# sensor.net
KiCad netlist of a schematic drawn in EAGLE
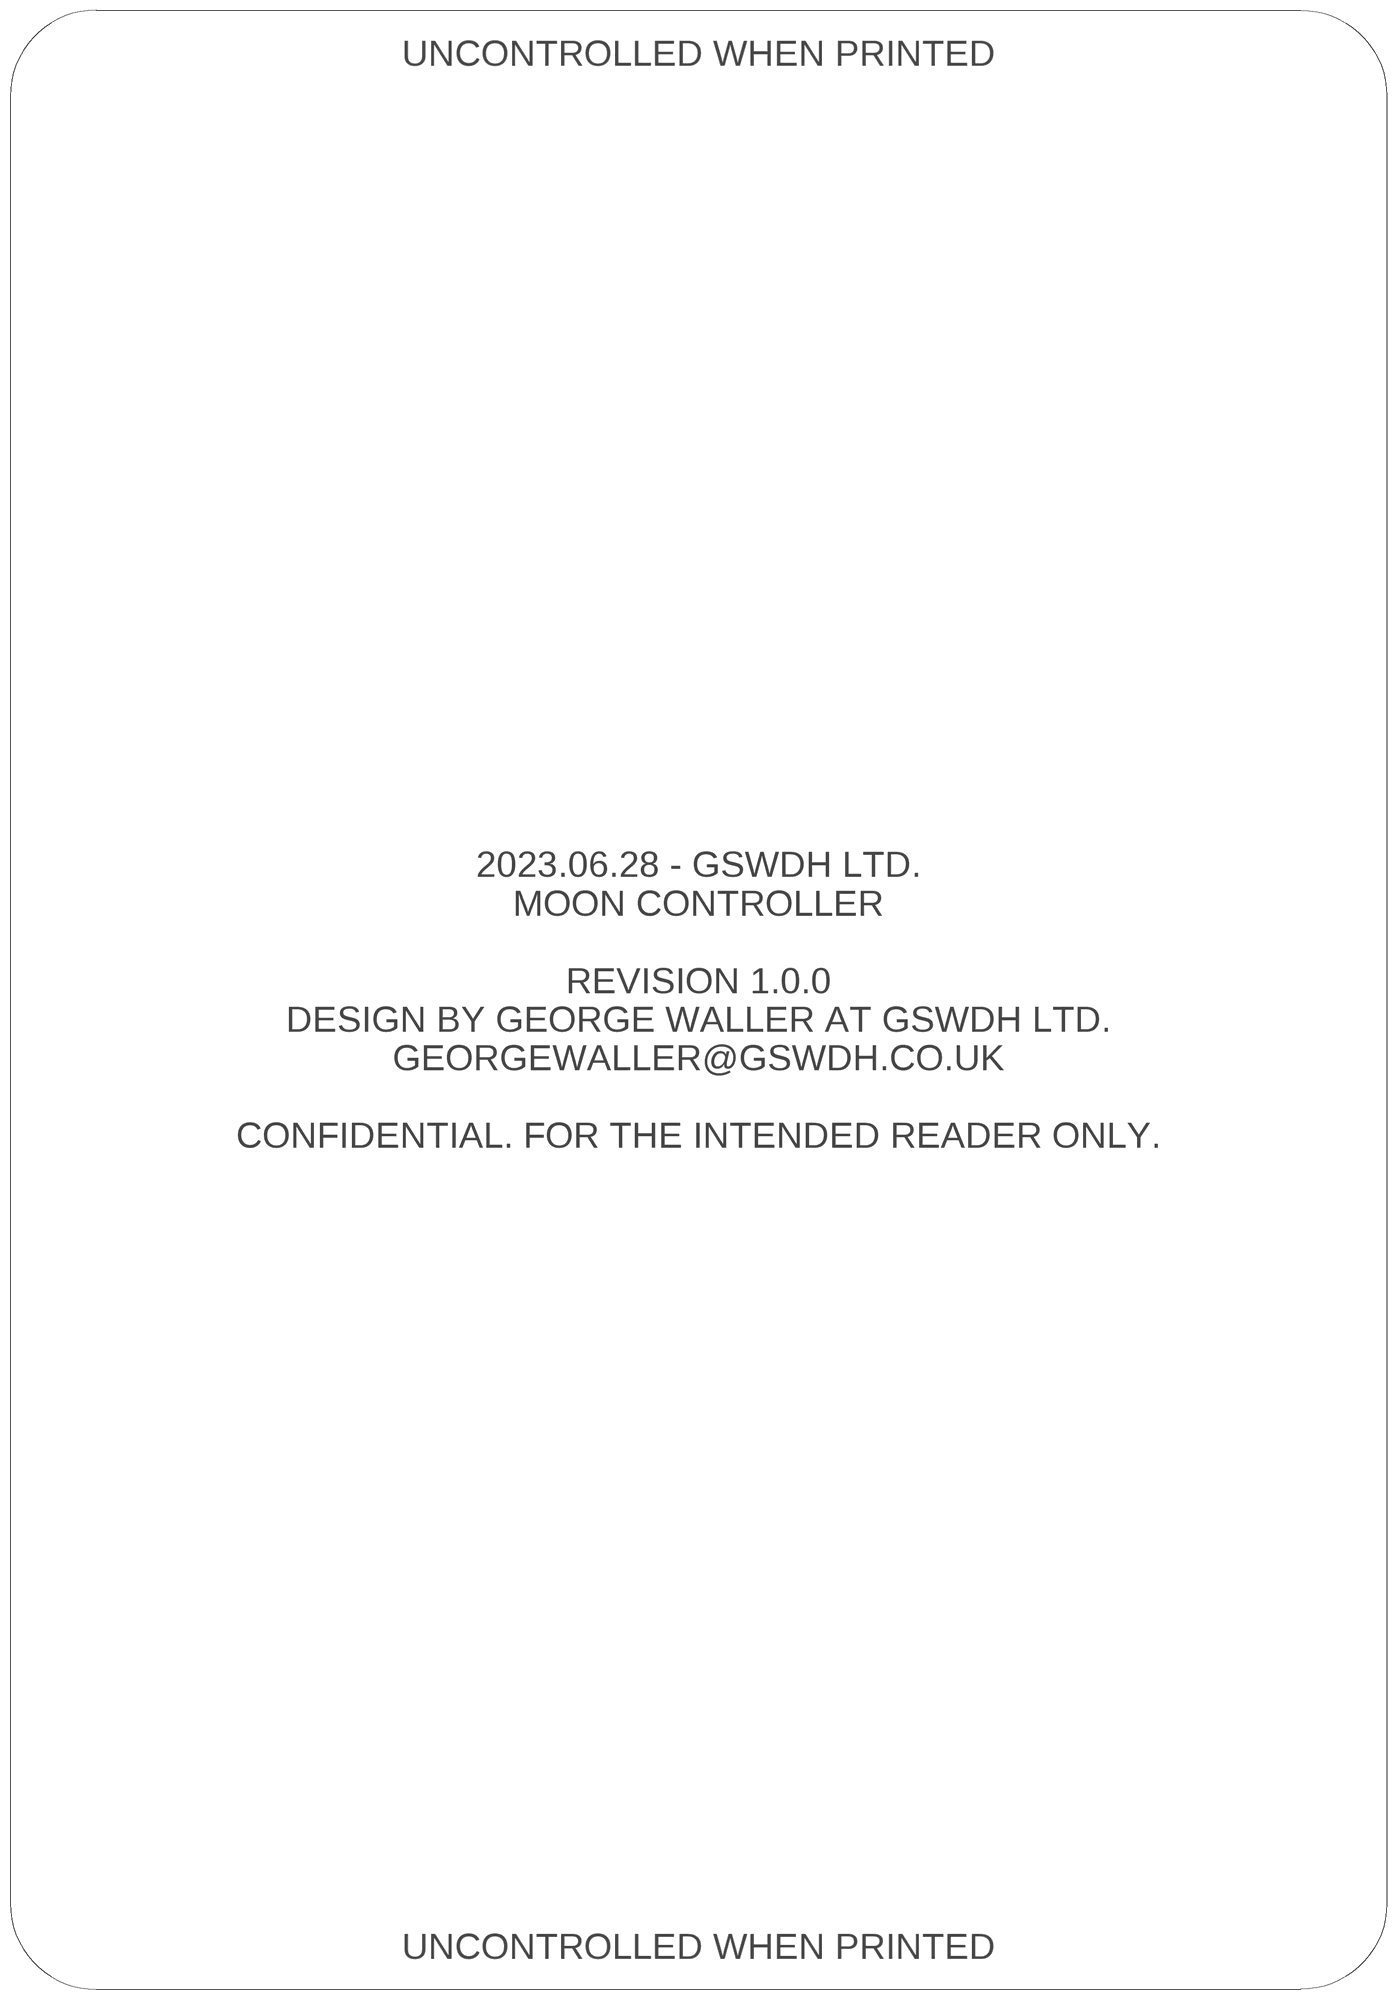
[diagram p0: schematic, sheet 1]
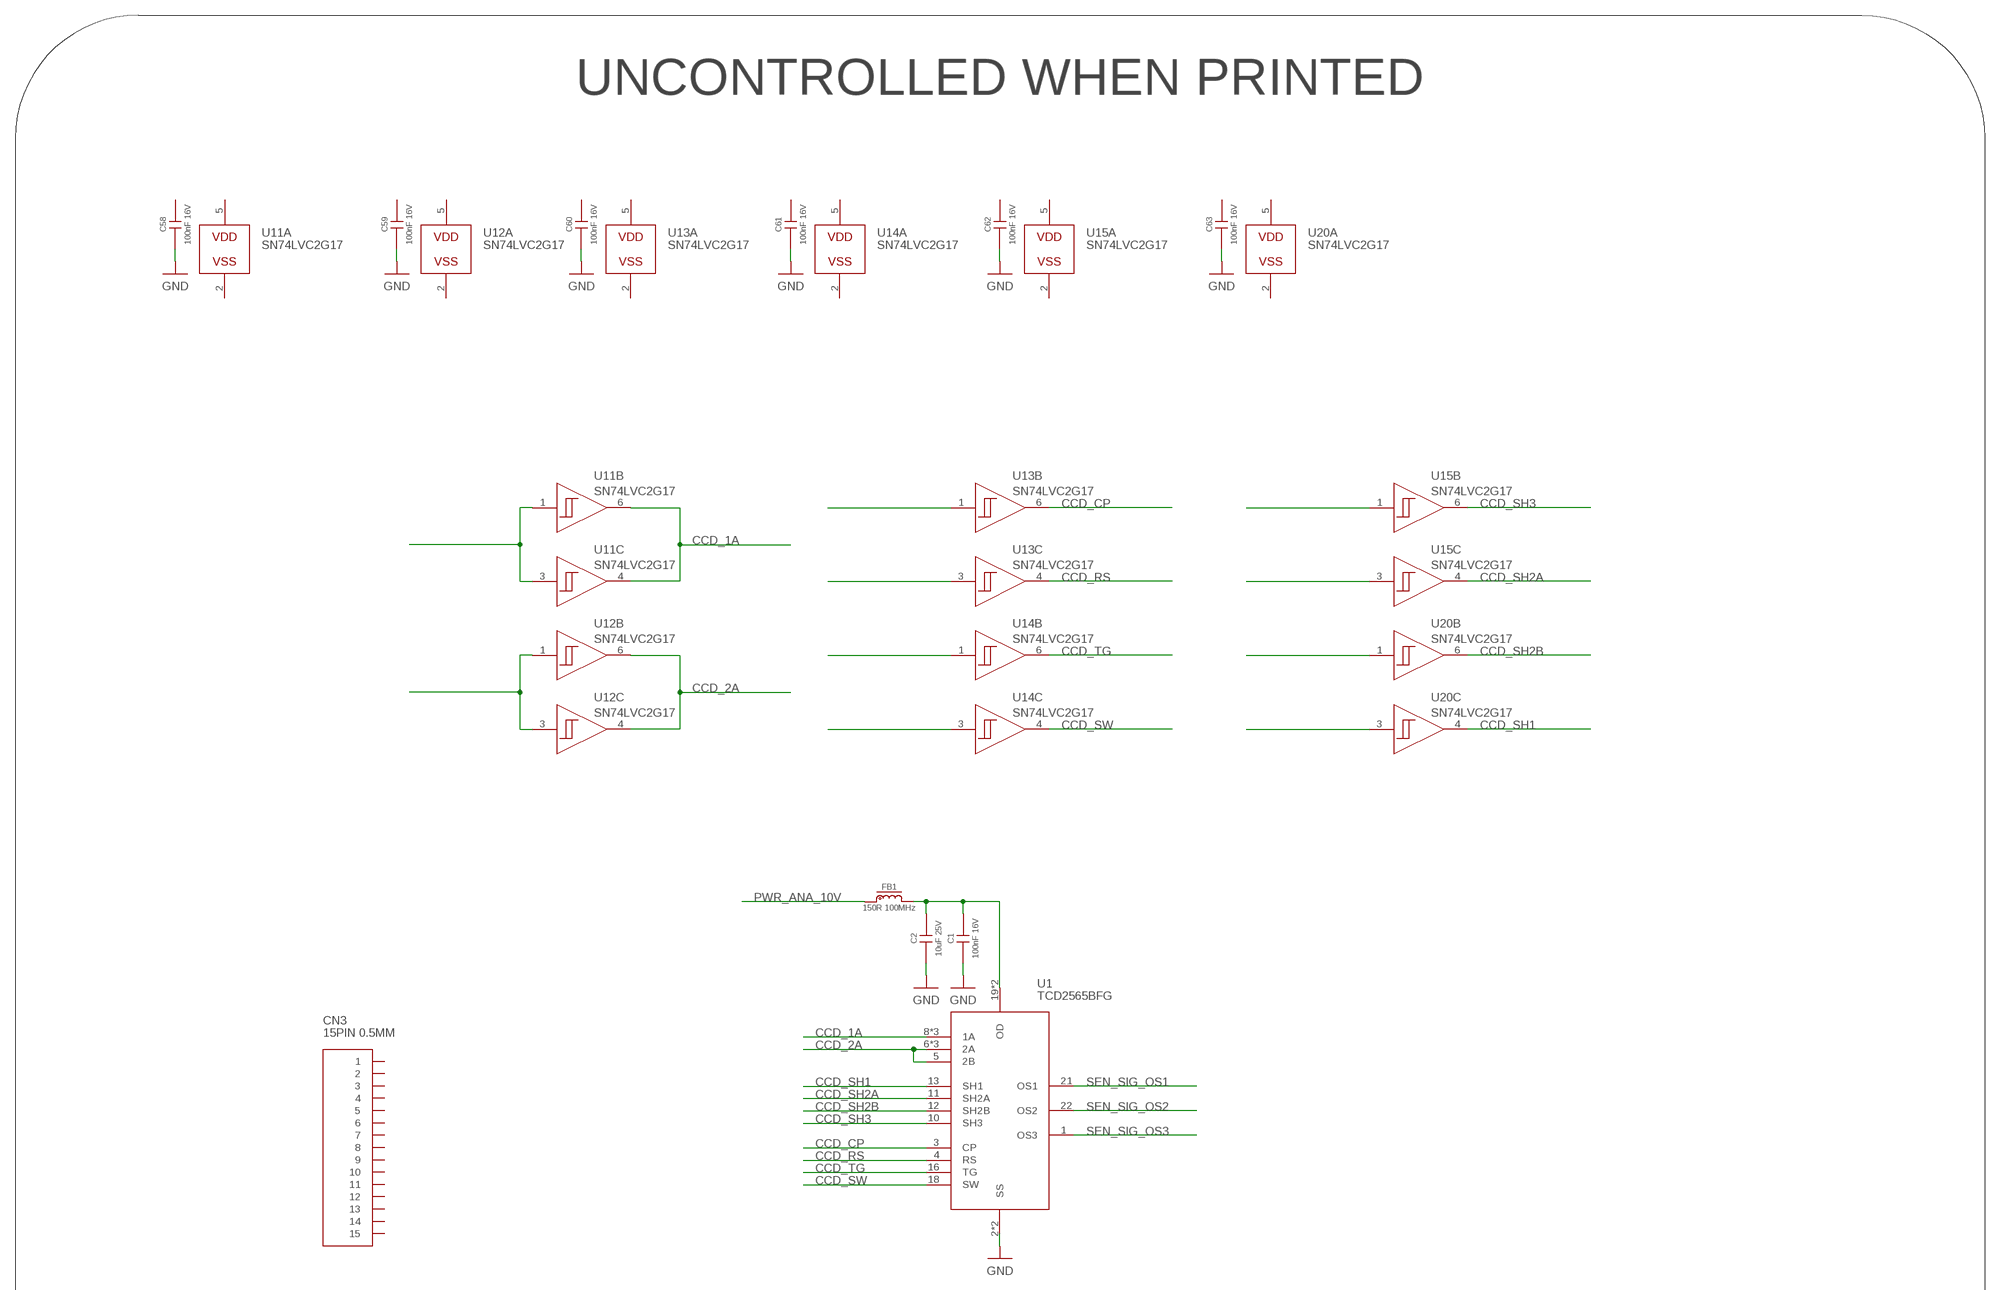
[diagram p1: schematic, sheet 2, part 1 of 2]
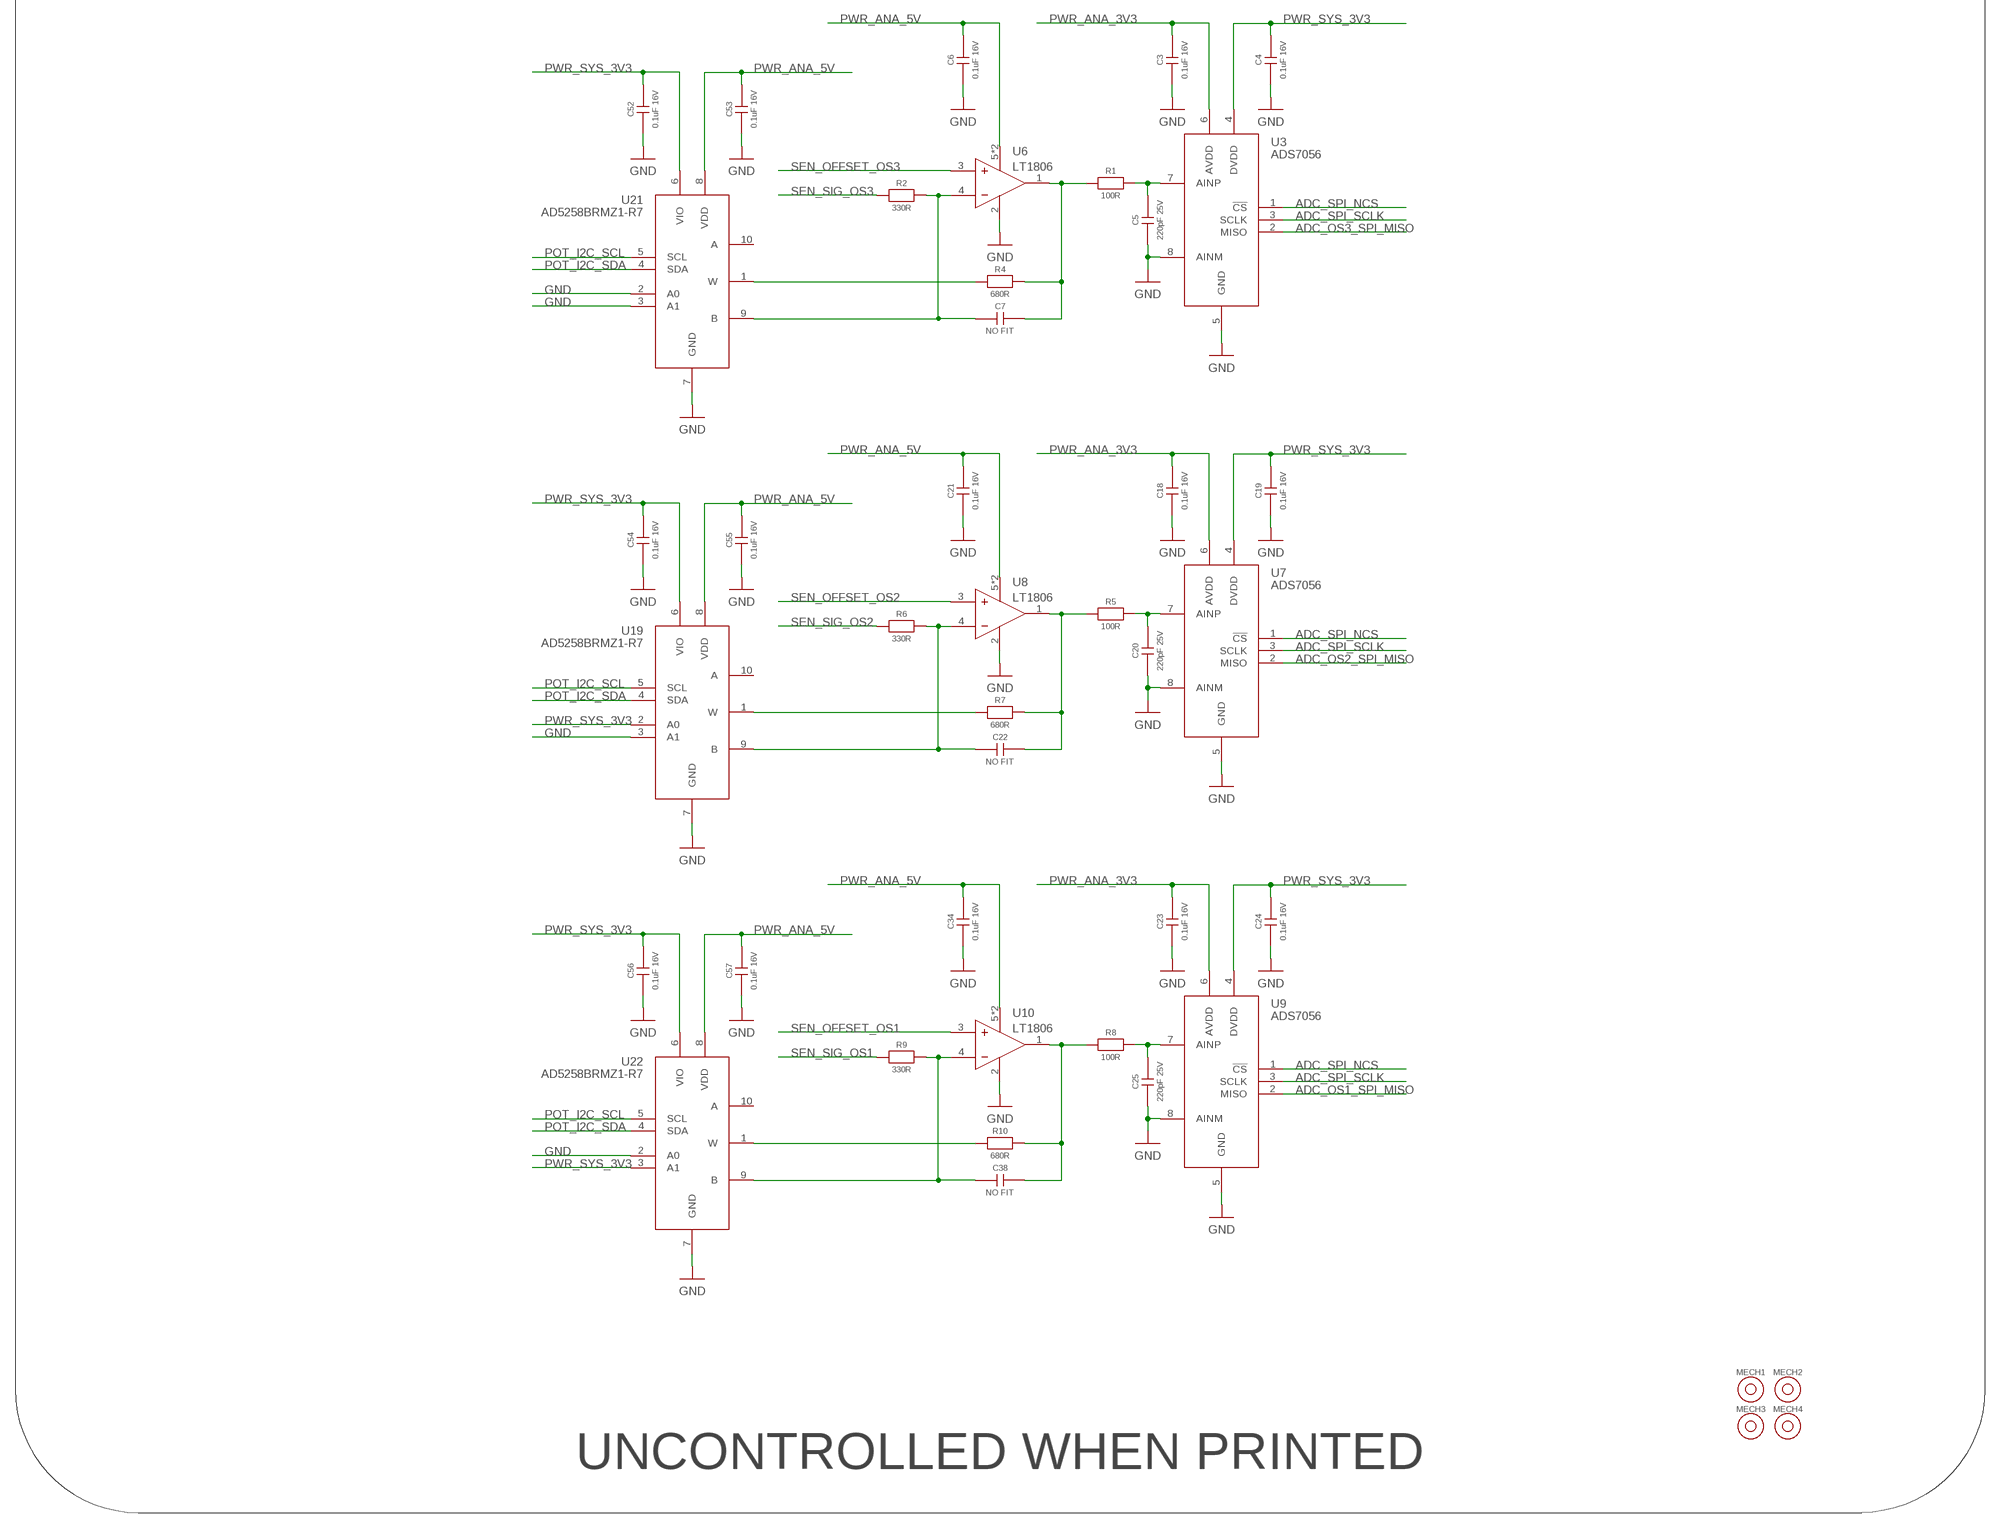
[diagram p2: schematic, sheet 2, part 2 of 2]
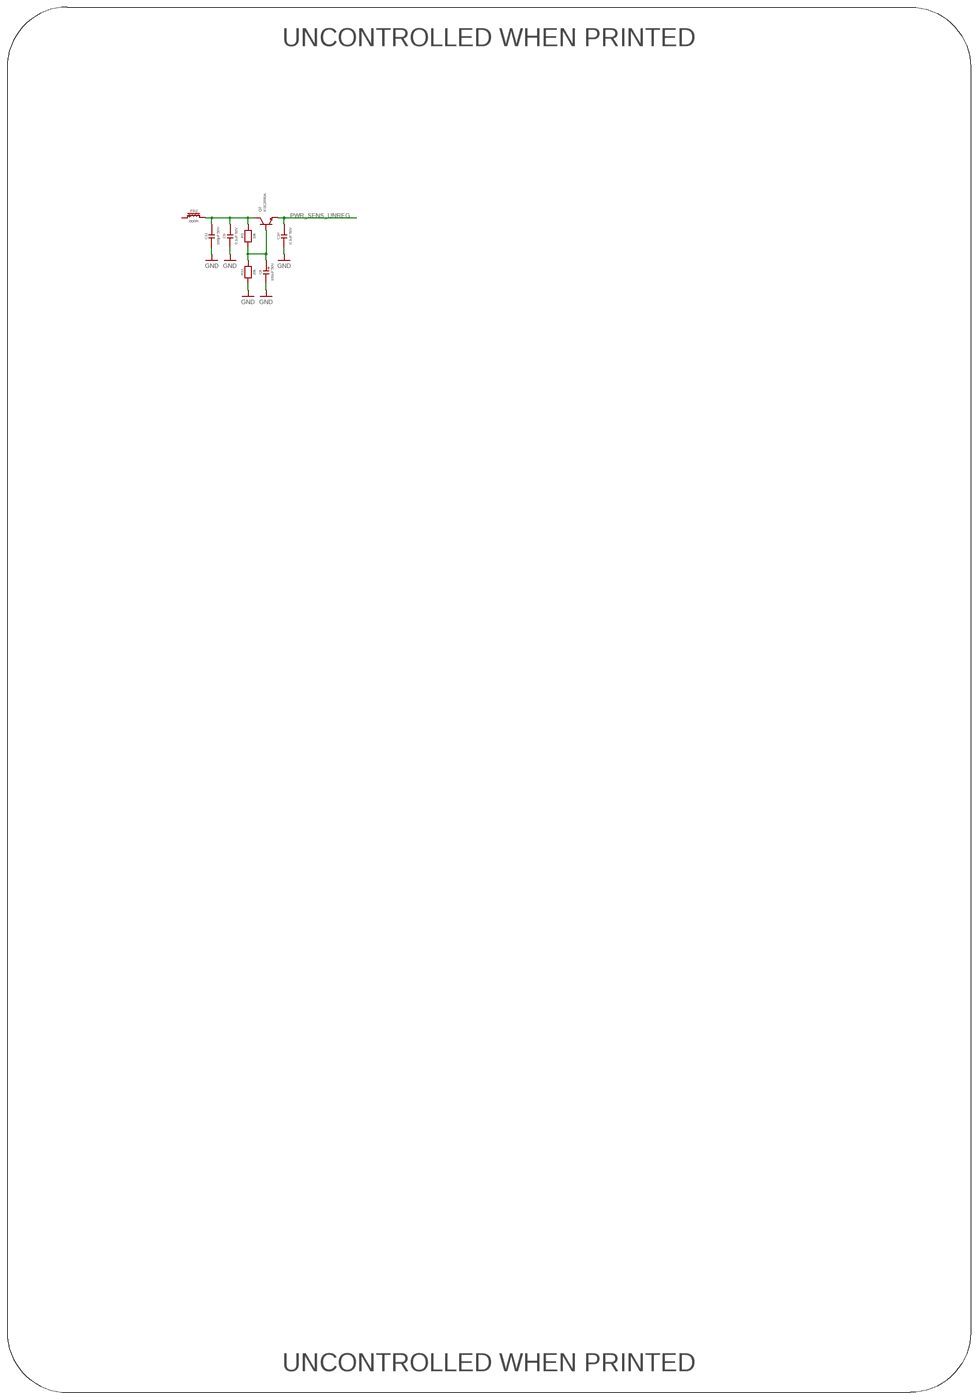
[diagram p3: schematic, sheet 3, overview]
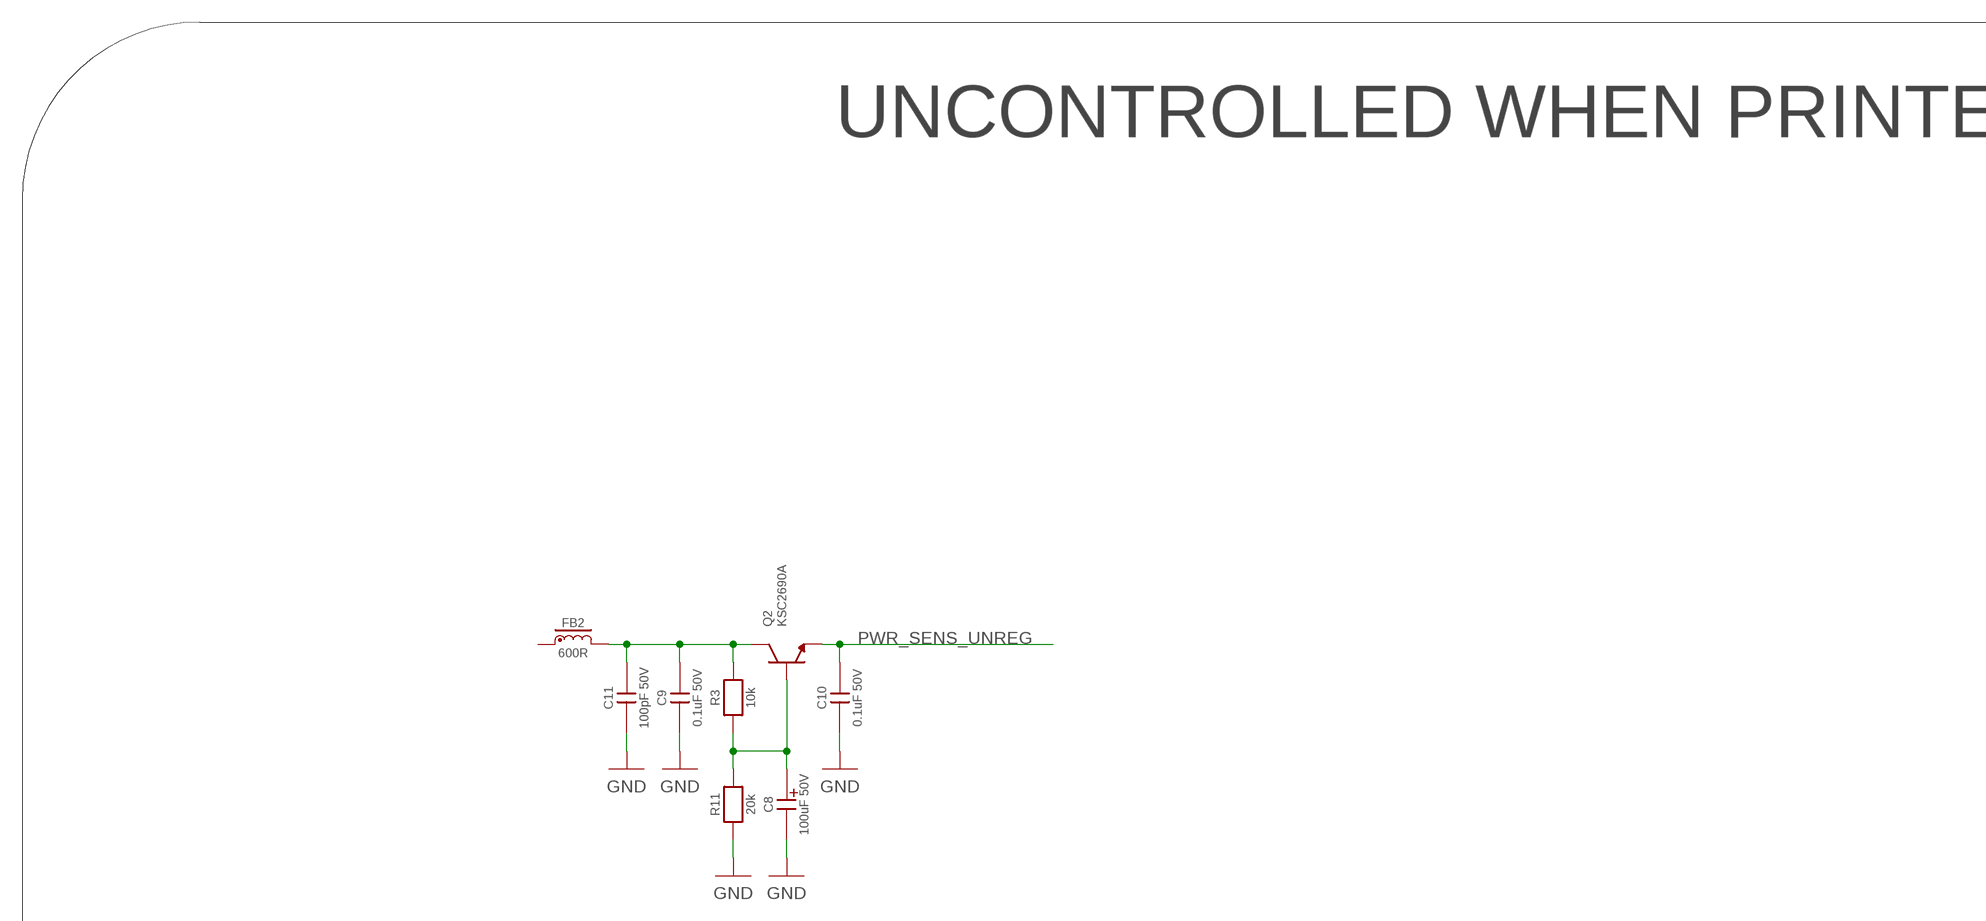
[diagram p4: schematic, sheet 3, part 1 of 4]
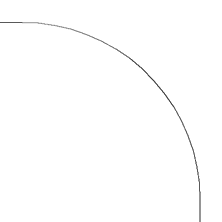
[diagram p5: schematic, sheet 3, part 2 of 4]
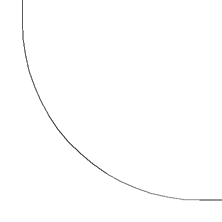
[diagram p6: schematic, sheet 3, part 3 of 4]
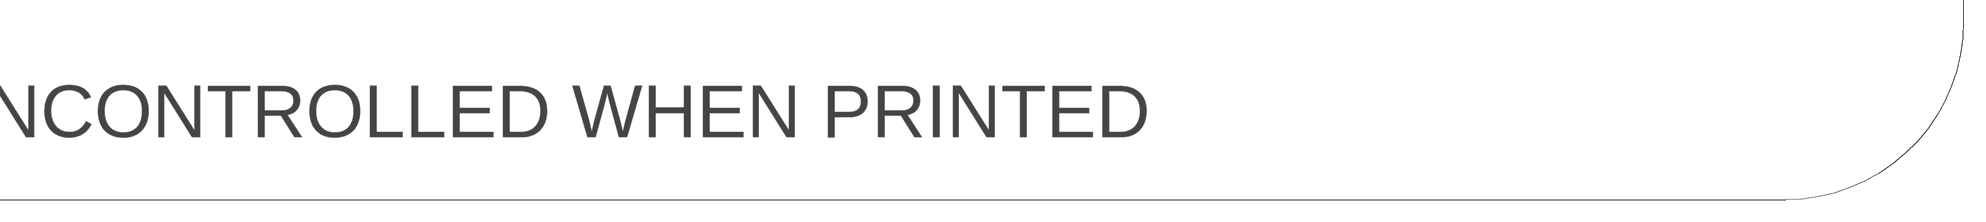
[diagram p7: schematic, sheet 3, part 4 of 4]

(export (version "E")
  (design (tool "Eeschema 10.0.6"))
  (components
    (comp (ref "C1")
      (value "100nF 16V")
      (footprint "eagle-import:0603")
      (libsource (lib "eagle-import") (part "CL10B104KO8WPNC"))
    )
    (comp (ref "C2")
      (value "10uF 25V")
      (footprint "eagle-import:1206")
      (fields
        (field (name "MANUFACTURER") "KEMET")
        (field (name "TOLERANCE") "±10%")
        (field (name "VOLTAGE") "25V")
      )
      (libsource (lib "eagle-import") (part "C1206C106K3RACAUTO"))
    )
    (comp (ref "C3")
      (value "0.1uF 16V")
      (footprint "eagle-import:0402")
      (fields
        (field (name "MANUFACTURER") "AVX Corporation")
        (field (name "TOLERANCE") "±10%")
        (field (name "VOLTAGE") "16V")
      )
      (libsource (lib "eagle-import") (part "0402YC104KAT2A"))
    )
    (comp (ref "C4")
      (value "0.1uF 16V")
      (footprint "eagle-import:0402")
      (fields
        (field (name "MANUFACTURER") "AVX Corporation")
        (field (name "TOLERANCE") "±10%")
        (field (name "VOLTAGE") "16V")
      )
      (libsource (lib "eagle-import") (part "0402YC104KAT2A"))
    )
    (comp (ref "C5")
      (value "220pF 25V")
      (footprint "eagle-import:0402")
      (fields
        (field (name "MANUFACTURER") "AVX Corporation")
        (field (name "TOLERANCE") "±1%")
        (field (name "VOLTAGE") "25V")
      )
      (libsource (lib "eagle-import") (part "04023A221FAT2A"))
    )
    (comp (ref "C6")
      (value "0.1uF 16V")
      (footprint "eagle-import:0402")
      (fields
        (field (name "MANUFACTURER") "AVX Corporation")
        (field (name "TOLERANCE") "±10%")
        (field (name "VOLTAGE") "16V")
      )
      (libsource (lib "eagle-import") (part "0402YC104KAT2A"))
    )
    (comp (ref "C7")
      (value "NO FIT")
      (footprint "eagle-import:0402")
      (fields
        (field (name "MANUFACTURER") "KEMET")
        (field (name "TOLERANCE") "±5%")
        (field (name "VOLTAGE") "25V")
      )
      (libsource (lib "eagle-import") (part "C0402C100J3GACAUTO"))
    )
    (comp (ref "C18")
      (value "0.1uF 16V")
      (footprint "eagle-import:0402")
      (fields
        (field (name "MANUFACTURER") "AVX Corporation")
        (field (name "TOLERANCE") "±10%")
        (field (name "VOLTAGE") "16V")
      )
      (libsource (lib "eagle-import") (part "0402YC104KAT2A"))
    )
    (comp (ref "C19")
      (value "0.1uF 16V")
      (footprint "eagle-import:0402")
      (fields
        (field (name "MANUFACTURER") "AVX Corporation")
        (field (name "TOLERANCE") "±10%")
        (field (name "VOLTAGE") "16V")
      )
      (libsource (lib "eagle-import") (part "0402YC104KAT2A"))
    )
    (comp (ref "C20")
      (value "220pF 25V")
      (footprint "eagle-import:0402")
      (fields
        (field (name "MANUFACTURER") "AVX Corporation")
        (field (name "TOLERANCE") "±1%")
        (field (name "VOLTAGE") "25V")
      )
      (libsource (lib "eagle-import") (part "04023A221FAT2A"))
    )
    (comp (ref "C21")
      (value "0.1uF 16V")
      (footprint "eagle-import:0402")
      (fields
        (field (name "MANUFACTURER") "AVX Corporation")
        (field (name "TOLERANCE") "±10%")
        (field (name "VOLTAGE") "16V")
      )
      (libsource (lib "eagle-import") (part "0402YC104KAT2A"))
    )
    (comp (ref "C22")
      (value "NO FIT")
      (footprint "eagle-import:0402")
      (fields
        (field (name "MANUFACTURER") "KEMET")
        (field (name "TOLERANCE") "±5%")
        (field (name "VOLTAGE") "25V")
      )
      (libsource (lib "eagle-import") (part "C0402C100J3GACAUTO"))
    )
    (comp (ref "C23")
      (value "0.1uF 16V")
      (footprint "eagle-import:0402")
      (fields
        (field (name "MANUFACTURER") "AVX Corporation")
        (field (name "TOLERANCE") "±10%")
        (field (name "VOLTAGE") "16V")
      )
      (libsource (lib "eagle-import") (part "0402YC104KAT2A"))
    )
    (comp (ref "C24")
      (value "0.1uF 16V")
      (footprint "eagle-import:0402")
      (fields
        (field (name "MANUFACTURER") "AVX Corporation")
        (field (name "TOLERANCE") "±10%")
        (field (name "VOLTAGE") "16V")
      )
      (libsource (lib "eagle-import") (part "0402YC104KAT2A"))
    )
    (comp (ref "C25")
      (value "220pF 25V")
      (footprint "eagle-import:0402")
      (fields
        (field (name "MANUFACTURER") "AVX Corporation")
        (field (name "TOLERANCE") "±1%")
        (field (name "VOLTAGE") "25V")
      )
      (libsource (lib "eagle-import") (part "04023A221FAT2A"))
    )
    (comp (ref "C34")
      (value "0.1uF 16V")
      (footprint "eagle-import:0402")
      (fields
        (field (name "MANUFACTURER") "AVX Corporation")
        (field (name "TOLERANCE") "±10%")
        (field (name "VOLTAGE") "16V")
      )
      (libsource (lib "eagle-import") (part "0402YC104KAT2A"))
    )
    (comp (ref "C38")
      (value "NO FIT")
      (footprint "eagle-import:0402")
      (fields
        (field (name "MANUFACTURER") "KEMET")
        (field (name "TOLERANCE") "±5%")
        (field (name "VOLTAGE") "25V")
      )
      (libsource (lib "eagle-import") (part "C0402C100J3GACAUTO"))
    )
    (comp (ref "C52")
      (value "0.1uF 16V")
      (footprint "eagle-import:0402")
      (fields
        (field (name "MANUFACTURER") "AVX Corporation")
        (field (name "TOLERANCE") "±10%")
        (field (name "VOLTAGE") "16V")
      )
      (libsource (lib "eagle-import") (part "0402YC104KAT2A"))
    )
    (comp (ref "C53")
      (value "0.1uF 16V")
      (footprint "eagle-import:0402")
      (fields
        (field (name "MANUFACTURER") "AVX Corporation")
        (field (name "TOLERANCE") "±10%")
        (field (name "VOLTAGE") "16V")
      )
      (libsource (lib "eagle-import") (part "0402YC104KAT2A"))
    )
    (comp (ref "C54")
      (value "0.1uF 16V")
      (footprint "eagle-import:0402")
      (fields
        (field (name "MANUFACTURER") "AVX Corporation")
        (field (name "TOLERANCE") "±10%")
        (field (name "VOLTAGE") "16V")
      )
      (libsource (lib "eagle-import") (part "0402YC104KAT2A"))
    )
    (comp (ref "C55")
      (value "0.1uF 16V")
      (footprint "eagle-import:0402")
      (fields
        (field (name "MANUFACTURER") "AVX Corporation")
        (field (name "TOLERANCE") "±10%")
        (field (name "VOLTAGE") "16V")
      )
      (libsource (lib "eagle-import") (part "0402YC104KAT2A"))
    )
    (comp (ref "C56")
      (value "0.1uF 16V")
      (footprint "eagle-import:0402")
      (fields
        (field (name "MANUFACTURER") "AVX Corporation")
        (field (name "TOLERANCE") "±10%")
        (field (name "VOLTAGE") "16V")
      )
      (libsource (lib "eagle-import") (part "0402YC104KAT2A"))
    )
    (comp (ref "C57")
      (value "0.1uF 16V")
      (footprint "eagle-import:0402")
      (fields
        (field (name "MANUFACTURER") "AVX Corporation")
        (field (name "TOLERANCE") "±10%")
        (field (name "VOLTAGE") "16V")
      )
      (libsource (lib "eagle-import") (part "0402YC104KAT2A"))
    )
    (comp (ref "C58")
      (value "100nF 16V")
      (footprint "eagle-import:0603")
      (libsource (lib "eagle-import") (part "CL10B104KO8WPNC"))
    )
    (comp (ref "C59")
      (value "100nF 16V")
      (footprint "eagle-import:0603")
      (libsource (lib "eagle-import") (part "CL10B104KO8WPNC"))
    )
    (comp (ref "C60")
      (value "100nF 16V")
      (footprint "eagle-import:0603")
      (libsource (lib "eagle-import") (part "CL10B104KO8WPNC"))
    )
    (comp (ref "C61")
      (value "100nF 16V")
      (footprint "eagle-import:0603")
      (libsource (lib "eagle-import") (part "CL10B104KO8WPNC"))
    )
    (comp (ref "C62")
      (value "100nF 16V")
      (footprint "eagle-import:0603")
      (libsource (lib "eagle-import") (part "CL10B104KO8WPNC"))
    )
    (comp (ref "C63")
      (value "100nF 16V")
      (footprint "eagle-import:0603")
      (libsource (lib "eagle-import") (part "CL10B104KO8WPNC"))
    )
    (comp (ref "CN3")
      (value "15PIN 0.5MM")
      (footprint "eagle-import:SFV15R-1STE1HLF")
      (libsource (lib "eagle-import") (part "SFV15R-1STE1HLF"))
    )
    (comp (ref "FB1")
      (value "150R 100MHz")
      (footprint "eagle-import:1206")
      (libsource (lib "eagle-import") (part "ILB1206ER151V"))
    )
    (comp (ref "MECH1")
      (value "6mm x 3mm")
      (footprint "eagle-import:MOUNTHOLE_6X3")
      (libsource (lib "eagle-import") (part "MOUNTHOLE"))
    )
    (comp (ref "MECH2")
      (value "6mm x 3mm")
      (footprint "eagle-import:MOUNTHOLE_6X3")
      (libsource (lib "eagle-import") (part "MOUNTHOLE"))
    )
    (comp (ref "MECH3")
      (value "6mm x 3mm")
      (footprint "eagle-import:MOUNTHOLE_6X3")
      (libsource (lib "eagle-import") (part "MOUNTHOLE"))
    )
    (comp (ref "MECH4")
      (value "6mm x 3mm")
      (footprint "eagle-import:MOUNTHOLE_6X3")
      (libsource (lib "eagle-import") (part "MOUNTHOLE"))
    )
    (comp (ref "R1")
      (value "100R")
      (footprint "eagle-import:0402")
      (libsource (lib "eagle-import") (part "RC0402FR-10100RL"))
    )
    (comp (ref "R2")
      (value "330R")
      (footprint "eagle-import:0402")
      (libsource (lib "eagle-import") (part "RC0402FR-07330RL"))
    )
    (comp (ref "R4")
      (value "680R")
      (footprint "eagle-import:0402")
      (libsource (lib "eagle-import") (part "RC0402FR-07680RL"))
    )
    (comp (ref "R5")
      (value "100R")
      (footprint "eagle-import:0402")
      (libsource (lib "eagle-import") (part "RC0402FR-10100RL"))
    )
    (comp (ref "R6")
      (value "330R")
      (footprint "eagle-import:0402")
      (libsource (lib "eagle-import") (part "RC0402FR-07330RL"))
    )
    (comp (ref "R7")
      (value "680R")
      (footprint "eagle-import:0402")
      (libsource (lib "eagle-import") (part "RC0402FR-07680RL"))
    )
    (comp (ref "R8")
      (value "100R")
      (footprint "eagle-import:0402")
      (libsource (lib "eagle-import") (part "RC0402FR-10100RL"))
    )
    (comp (ref "R9")
      (value "330R")
      (footprint "eagle-import:0402")
      (libsource (lib "eagle-import") (part "RC0402FR-07330RL"))
    )
    (comp (ref "R10")
      (value "680R")
      (footprint "eagle-import:0402")
      (libsource (lib "eagle-import") (part "RC0402FR-07680RL"))
    )
    (comp (ref "U1")
      (value "TCD2565BFG")
      (footprint "eagle-import:TCD2565BFG")
      (libsource (lib "eagle-import") (part "TCD2565BFG"))
    )
    (comp (ref "U3")
      (value "ADS7056")
      (footprint "eagle-import:X2QFN8")
      (libsource (lib "eagle-import") (part "ADS7056IRUGR"))
    )
    (comp (ref "U6")
      (value "LT1806")
      (footprint "eagle-import:SOT23-6")
      (libsource (lib "eagle-import") (part "LT1806CS6#TRMPBF"))
    )
    (comp (ref "U7")
      (value "ADS7056")
      (footprint "eagle-import:X2QFN8")
      (libsource (lib "eagle-import") (part "ADS7056IRUGR"))
    )
    (comp (ref "U8")
      (value "LT1806")
      (footprint "eagle-import:SOT23-6")
      (libsource (lib "eagle-import") (part "LT1806CS6#TRMPBF"))
    )
    (comp (ref "U9")
      (value "ADS7056")
      (footprint "eagle-import:X2QFN8")
      (libsource (lib "eagle-import") (part "ADS7056IRUGR"))
    )
    (comp (ref "U10")
      (value "LT1806")
      (footprint "eagle-import:SOT23-6")
      (libsource (lib "eagle-import") (part "LT1806CS6#TRMPBF"))
    )
    (comp (ref "U11")
      (value "SN74LVC2G17")
      (footprint "eagle-import:SOT23-6")
      (libsource (lib "eagle-import") (part "SN74LVC2G17DBVR"))
    )
    (comp (ref "U12")
      (value "SN74LVC2G17")
      (footprint "eagle-import:SOT23-6")
      (libsource (lib "eagle-import") (part "SN74LVC2G17DBVR"))
    )
    (comp (ref "U13")
      (value "SN74LVC2G17")
      (footprint "eagle-import:SOT23-6")
      (libsource (lib "eagle-import") (part "SN74LVC2G17DBVR"))
    )
    (comp (ref "U14")
      (value "SN74LVC2G17")
      (footprint "eagle-import:SOT23-6")
      (libsource (lib "eagle-import") (part "SN74LVC2G17DBVR"))
    )
    (comp (ref "U15")
      (value "SN74LVC2G17")
      (footprint "eagle-import:SOT23-6")
      (libsource (lib "eagle-import") (part "SN74LVC2G17DBVR"))
    )
    (comp (ref "U19")
      (value "AD5258BRMZ1-R7")
      (footprint "eagle-import:MSOP10")
      (libsource (lib "eagle-import") (part "AD5258BRMZ1-R7"))
    )
    (comp (ref "U20")
      (value "SN74LVC2G17")
      (footprint "eagle-import:SOT23-6")
      (libsource (lib "eagle-import") (part "SN74LVC2G17DBVR"))
    )
    (comp (ref "U21")
      (value "AD5258BRMZ1-R7")
      (footprint "eagle-import:MSOP10")
      (libsource (lib "eagle-import") (part "AD5258BRMZ1-R7"))
    )
    (comp (ref "U22")
      (value "AD5258BRMZ1-R7")
      (footprint "eagle-import:MSOP10")
      (libsource (lib "eagle-import") (part "AD5258BRMZ1-R7"))
    )
    (comp (ref "C8")
      (value "100uF 50V")
      (footprint "eagle-import:8MM_RADIAL_3.5MM_PITCH")
      (libsource (lib "eagle-import") (part "107CKR050M"))
    )
    (comp (ref "C9")
      (value "0.1uF 50V")
      (footprint "eagle-import:0603")
      (fields
        (field (name "MANUFACTURER") "AVX Corporation")
        (field (name "TOLERANCE") "±5%")
        (field (name "VOLTAGE") "50V")
      )
      (libsource (lib "eagle-import") (part "06035C104JAT2A"))
    )
    (comp (ref "C10")
      (value "0.1uF 50V")
      (footprint "eagle-import:0603")
      (fields
        (field (name "MANUFACTURER") "AVX Corporation")
        (field (name "TOLERANCE") "±5%")
        (field (name "VOLTAGE") "50V")
      )
      (libsource (lib "eagle-import") (part "06035C104JAT2A"))
    )
    (comp (ref "C11")
      (value "100pF 50V")
      (footprint "eagle-import:0603")
      (fields
        (field (name "MANUFACTURER") "AVX Corporation")
        (field (name "TOLERANCE") "±5%")
        (field (name "VOLTAGE") "50V")
      )
      (libsource (lib "eagle-import") (part "06035A101J4T4A"))
    )
    (comp (ref "FB2")
      (value "600R")
      (footprint "eagle-import:0603")
      (libsource (lib "eagle-import") (part "742792651"))
    )
    (comp (ref "Q2")
      (value "KSC2690A")
      (footprint "eagle-import:TO126V")
      (libsource (lib "eagle-import") (part "KSC2690AV"))
    )
    (comp (ref "R3")
      (value "10k")
      (footprint "eagle-import:0603")
      (fields
        (field (name "MANUFACTURER") "Vishay Dale")
        (field (name "POWER") "0.1W, 1/10W")
        (field (name "TOLERANCE") "±1%")
      )
      (libsource (lib "eagle-import") (part "CRCW060310K0FKTA"))
    )
    (comp (ref "R11")
      (value "20k")
      (footprint "eagle-import:0603")
      (fields
        (field (name "MANUFACTURER") "Vishay Dale")
        (field (name "POWER") "0.1W, 1/10W")
        (field (name "TOLERANCE") "±1%")
      )
      (libsource (lib "eagle-import") (part "CRCW060320K0FKEA"))
    )
  )
  (nets
    (net (code "1") (name "ADC_OS1_SPI_MISO") (class "Default")
      (node (ref "U9") (pin "2") (pinfunction "MISO_2") (pintype "bidirectional"))
    )
    (net (code "2") (name "ADC_OS2_SPI_MISO") (class "Default")
      (node (ref "U7") (pin "2") (pinfunction "MISO_2") (pintype "bidirectional"))
    )
    (net (code "3") (name "ADC_OS3_SPI_MISO") (class "Default")
      (node (ref "U3") (pin "2") (pinfunction "MISO_2") (pintype "bidirectional"))
    )
    (net (code "4") (name "ADC_SPI_NCS") (class "Default")
      (node (ref "U3") (pin "1") (pinfunction "~{CS}_1") (pintype "bidirectional"))
      (node (ref "U7") (pin "1") (pinfunction "~{CS}_1") (pintype "bidirectional"))
      (node (ref "U9") (pin "1") (pinfunction "~{CS}_1") (pintype "bidirectional"))
    )
    (net (code "5") (name "ADC_SPI_SCLK") (class "Default")
      (node (ref "U3") (pin "3") (pinfunction "SCLK_3") (pintype "bidirectional"))
      (node (ref "U7") (pin "3") (pinfunction "SCLK_3") (pintype "bidirectional"))
      (node (ref "U9") (pin "3") (pinfunction "SCLK_3") (pintype "bidirectional"))
    )
    (net (code "6") (name "CCD_1A") (class "Default")
      (node (ref "U1") (pin "15") (pinfunction "1A_15") (pintype "bidirectional"))
      (node (ref "U1") (pin "17") (pinfunction "1A_17") (pintype "bidirectional"))
      (node (ref "U1") (pin "8") (pinfunction "1A_8") (pintype "bidirectional"))
      (node (ref "U11") (pin "4") (pinfunction "Q_4") (pintype "bidirectional"))
      (node (ref "U11") (pin "6") (pinfunction "Q_6") (pintype "bidirectional"))
    )
    (net (code "7") (name "CCD_2A") (class "Default")
      (node (ref "U1") (pin "14") (pinfunction "2A_14") (pintype "bidirectional"))
      (node (ref "U1") (pin "5") (pinfunction "2B_5") (pintype "bidirectional"))
      (node (ref "U1") (pin "6") (pinfunction "2A_6") (pintype "bidirectional"))
      (node (ref "U1") (pin "9") (pinfunction "2A_9") (pintype "bidirectional"))
      (node (ref "U12") (pin "4") (pinfunction "Q_4") (pintype "bidirectional"))
      (node (ref "U12") (pin "6") (pinfunction "Q_6") (pintype "bidirectional"))
    )
    (net (code "8") (name "CCD_CP") (class "Default")
      (node (ref "U1") (pin "3") (pinfunction "CP_3") (pintype "bidirectional"))
      (node (ref "U13") (pin "6") (pinfunction "Q_6") (pintype "bidirectional"))
    )
    (net (code "9") (name "CCD_RS") (class "Default")
      (node (ref "U1") (pin "4") (pinfunction "RS_4") (pintype "bidirectional"))
      (node (ref "U13") (pin "4") (pinfunction "Q_4") (pintype "bidirectional"))
    )
    (net (code "10") (name "CCD_SH1") (class "Default")
      (node (ref "U1") (pin "13") (pinfunction "SH1_13") (pintype "bidirectional"))
      (node (ref "U20") (pin "4") (pinfunction "Q_4") (pintype "bidirectional"))
    )
    (net (code "11") (name "CCD_SH2A") (class "Default")
      (node (ref "U1") (pin "11") (pinfunction "SH2A_11") (pintype "bidirectional"))
      (node (ref "U15") (pin "4") (pinfunction "Q_4") (pintype "bidirectional"))
    )
    (net (code "12") (name "CCD_SH2B") (class "Default")
      (node (ref "U1") (pin "12") (pinfunction "SH2B_12") (pintype "bidirectional"))
      (node (ref "U20") (pin "6") (pinfunction "Q_6") (pintype "bidirectional"))
    )
    (net (code "13") (name "CCD_SH3") (class "Default")
      (node (ref "U1") (pin "10") (pinfunction "SH3_10") (pintype "bidirectional"))
      (node (ref "U15") (pin "6") (pinfunction "Q_6") (pintype "bidirectional"))
    )
    (net (code "14") (name "CCD_SW") (class "Default")
      (node (ref "U1") (pin "18") (pinfunction "SW_18") (pintype "bidirectional"))
      (node (ref "U14") (pin "4") (pinfunction "Q_4") (pintype "bidirectional"))
    )
    (net (code "15") (name "CCD_TG") (class "Default")
      (node (ref "U1") (pin "16") (pinfunction "TG_16") (pintype "bidirectional"))
      (node (ref "U14") (pin "6") (pinfunction "Q_6") (pintype "bidirectional"))
    )
    (net (code "16") (name "GND") (class "Default")
      (node (ref "C1") (pin "1") (pinfunction "1_1") (pintype "bidirectional"))
      (node (ref "C10") (pin "1") (pinfunction "1_1") (pintype "bidirectional"))
      (node (ref "C11") (pin "1") (pinfunction "1_1") (pintype "bidirectional"))
      (node (ref "C18") (pin "1") (pinfunction "1_1") (pintype "bidirectional"))
      (node (ref "C19") (pin "1") (pinfunction "1_1") (pintype "bidirectional"))
      (node (ref "C2") (pin "1") (pinfunction "1_1") (pintype "bidirectional"))
      (node (ref "C20") (pin "1") (pinfunction "1_1") (pintype "bidirectional"))
      (node (ref "C21") (pin "1") (pinfunction "1_1") (pintype "bidirectional"))
      (node (ref "C23") (pin "1") (pinfunction "1_1") (pintype "bidirectional"))
      (node (ref "C24") (pin "1") (pinfunction "1_1") (pintype "bidirectional"))
      (node (ref "C25") (pin "1") (pinfunction "1_1") (pintype "bidirectional"))
      (node (ref "C3") (pin "1") (pinfunction "1_1") (pintype "bidirectional"))
      (node (ref "C34") (pin "1") (pinfunction "1_1") (pintype "bidirectional"))
      (node (ref "C4") (pin "1") (pinfunction "1_1") (pintype "bidirectional"))
      (node (ref "C5") (pin "1") (pinfunction "1_1") (pintype "bidirectional"))
      (node (ref "C52") (pin "1") (pinfunction "1_1") (pintype "bidirectional"))
      (node (ref "C53") (pin "1") (pinfunction "1_1") (pintype "bidirectional"))
      (node (ref "C54") (pin "1") (pinfunction "1_1") (pintype "bidirectional"))
      (node (ref "C55") (pin "1") (pinfunction "1_1") (pintype "bidirectional"))
      (node (ref "C56") (pin "1") (pinfunction "1_1") (pintype "bidirectional"))
      (node (ref "C57") (pin "1") (pinfunction "1_1") (pintype "bidirectional"))
      (node (ref "C58") (pin "1") (pinfunction "1_1") (pintype "bidirectional"))
      (node (ref "C59") (pin "1") (pinfunction "1_1") (pintype "bidirectional"))
      (node (ref "C6") (pin "1") (pinfunction "1_1") (pintype "bidirectional"))
      (node (ref "C60") (pin "1") (pinfunction "1_1") (pintype "bidirectional"))
      (node (ref "C61") (pin "1") (pinfunction "1_1") (pintype "bidirectional"))
      (node (ref "C62") (pin "1") (pinfunction "1_1") (pintype "bidirectional"))
      (node (ref "C63") (pin "1") (pinfunction "1_1") (pintype "bidirectional"))
      (node (ref "C8") (pin "N") (pinfunction "K_N") (pintype "bidirectional"))
      (node (ref "C9") (pin "1") (pinfunction "1_1") (pintype "bidirectional"))
      (node (ref "R11") (pin "1") (pinfunction "1_1") (pintype "bidirectional"))
      (node (ref "U1") (pin "2") (pinfunction "SS_2") (pintype "bidirectional"))
      (node (ref "U1") (pin "7") (pinfunction "SS_7") (pintype "bidirectional"))
      (node (ref "U10") (pin "2") (pinfunction "V-_2") (pintype "bidirectional"))
      (node (ref "U19") (pin "3") (pinfunction "A1_3") (pintype "bidirectional"))
      (node (ref "U19") (pin "7") (pinfunction "GND_7") (pintype "bidirectional"))
      (node (ref "U21") (pin "2") (pinfunction "A0_2") (pintype "bidirectional"))
      (node (ref "U21") (pin "3") (pinfunction "A1_3") (pintype "bidirectional"))
      (node (ref "U21") (pin "7") (pinfunction "GND_7") (pintype "bidirectional"))
      (node (ref "U22") (pin "2") (pinfunction "A0_2") (pintype "bidirectional"))
      (node (ref "U22") (pin "7") (pinfunction "GND_7") (pintype "bidirectional"))
      (node (ref "U3") (pin "5") (pinfunction "GND_5") (pintype "bidirectional"))
      (node (ref "U3") (pin "8") (pinfunction "AINM_8") (pintype "bidirectional"))
      (node (ref "U6") (pin "2") (pinfunction "V-_2") (pintype "bidirectional"))
      (node (ref "U7") (pin "5") (pinfunction "GND_5") (pintype "bidirectional"))
      (node (ref "U7") (pin "8") (pinfunction "AINM_8") (pintype "bidirectional"))
      (node (ref "U8") (pin "2") (pinfunction "V-_2") (pintype "bidirectional"))
      (node (ref "U9") (pin "5") (pinfunction "GND_5") (pintype "bidirectional"))
      (node (ref "U9") (pin "8") (pinfunction "AINM_8") (pintype "bidirectional"))
    )
    (net (code "17") (name "Net-(C1-Pad2)") (class "Default")
      (node (ref "C1") (pin "2") (pinfunction "2_2") (pintype "bidirectional"))
      (node (ref "C2") (pin "2") (pinfunction "2_2") (pintype "bidirectional"))
      (node (ref "FB1") (pin "2") (pinfunction "2_2") (pintype "bidirectional"))
      (node (ref "U1") (pin "19") (pinfunction "OD_19") (pintype "bidirectional"))
      (node (ref "U1") (pin "20") (pinfunction "OD_20") (pintype "bidirectional"))
    )
    (net (code "18") (name "Net-(C8-A)") (class "Default")
      (node (ref "C8") (pin "P") (pinfunction "A_P") (pintype "bidirectional"))
      (node (ref "Q2") (pin "3") (pinfunction "B_3") (pintype "bidirectional"))
      (node (ref "R11") (pin "2") (pinfunction "2_2") (pintype "bidirectional"))
      (node (ref "R3") (pin "1") (pinfunction "1_1") (pintype "bidirectional"))
    )
    (net (code "19") (name "Net-(Q2-C)") (class "Default")
      (node (ref "C11") (pin "2") (pinfunction "2_2") (pintype "bidirectional"))
      (node (ref "C9") (pin "2") (pinfunction "2_2") (pintype "bidirectional"))
      (node (ref "FB2") (pin "2") (pinfunction "2_2") (pintype "bidirectional"))
      (node (ref "Q2") (pin "2") (pinfunction "C_2") (pintype "bidirectional"))
      (node (ref "R3") (pin "2") (pinfunction "2_2") (pintype "bidirectional"))
    )
    (net (code "20") (name "Net-(U3-AINP)") (class "Default")
      (node (ref "C5") (pin "2") (pinfunction "2_2") (pintype "bidirectional"))
      (node (ref "R1") (pin "2") (pinfunction "2_2") (pintype "bidirectional"))
      (node (ref "U3") (pin "7") (pinfunction "AINP_7") (pintype "bidirectional"))
    )
    (net (code "21") (name "Net-(U6-OUT)") (class "Default")
      (node (ref "C7") (pin "2") (pinfunction "2_2") (pintype "bidirectional"))
      (node (ref "R1") (pin "1") (pinfunction "1_1") (pintype "bidirectional"))
      (node (ref "R4") (pin "2") (pinfunction "2_2") (pintype "bidirectional"))
      (node (ref "U6") (pin "1") (pinfunction "OUT_1") (pintype "bidirectional"))
    )
    (net (code "22") (name "Net-(U7-AINP)") (class "Default")
      (node (ref "C20") (pin "2") (pinfunction "2_2") (pintype "bidirectional"))
      (node (ref "R5") (pin "2") (pinfunction "2_2") (pintype "bidirectional"))
      (node (ref "U7") (pin "7") (pinfunction "AINP_7") (pintype "bidirectional"))
    )
    (net (code "23") (name "Net-(U8-OUT)") (class "Default")
      (node (ref "C22") (pin "2") (pinfunction "2_2") (pintype "bidirectional"))
      (node (ref "R5") (pin "1") (pinfunction "1_1") (pintype "bidirectional"))
      (node (ref "R7") (pin "2") (pinfunction "2_2") (pintype "bidirectional"))
      (node (ref "U8") (pin "1") (pinfunction "OUT_1") (pintype "bidirectional"))
    )
    (net (code "24") (name "Net-(U9-AINP)") (class "Default")
      (node (ref "C25") (pin "2") (pinfunction "2_2") (pintype "bidirectional"))
      (node (ref "R8") (pin "2") (pinfunction "2_2") (pintype "bidirectional"))
      (node (ref "U9") (pin "7") (pinfunction "AINP_7") (pintype "bidirectional"))
    )
    (net (code "25") (name "Net-(U10--)") (class "Default")
      (node (ref "C38") (pin "1") (pinfunction "1_1") (pintype "bidirectional"))
      (node (ref "R9") (pin "2") (pinfunction "2_2") (pintype "bidirectional"))
      (node (ref "U10") (pin "4") (pinfunction "-_4") (pintype "bidirectional"))
      (node (ref "U22") (pin "9") (pinfunction "B_9") (pintype "bidirectional"))
    )
    (net (code "26") (name "Net-(U10-OUT)") (class "Default")
      (node (ref "C38") (pin "2") (pinfunction "2_2") (pintype "bidirectional"))
      (node (ref "R10") (pin "2") (pinfunction "2_2") (pintype "bidirectional"))
      (node (ref "R8") (pin "1") (pinfunction "1_1") (pintype "bidirectional"))
      (node (ref "U10") (pin "1") (pinfunction "OUT_1") (pintype "bidirectional"))
    )
    (net (code "27") (name "Net-(U11B-A)") (class "Default")
      (node (ref "U11") (pin "1") (pinfunction "A_1") (pintype "bidirectional"))
      (node (ref "U11") (pin "3") (pinfunction "A_3") (pintype "bidirectional"))
    )
    (net (code "28") (name "Net-(U12B-A)") (class "Default")
      (node (ref "U12") (pin "1") (pinfunction "A_1") (pintype "bidirectional"))
      (node (ref "U12") (pin "3") (pinfunction "A_3") (pintype "bidirectional"))
    )
    (net (code "29") (name "Net-(U19-B)") (class "Default")
      (node (ref "C22") (pin "1") (pinfunction "1_1") (pintype "bidirectional"))
      (node (ref "R6") (pin "2") (pinfunction "2_2") (pintype "bidirectional"))
      (node (ref "U19") (pin "9") (pinfunction "B_9") (pintype "bidirectional"))
      (node (ref "U8") (pin "4") (pinfunction "-_4") (pintype "bidirectional"))
    )
    (net (code "30") (name "Net-(U19-W)") (class "Default")
      (node (ref "R7") (pin "1") (pinfunction "1_1") (pintype "bidirectional"))
      (node (ref "U19") (pin "1") (pinfunction "W_1") (pintype "bidirectional"))
    )
    (net (code "31") (name "Net-(U21-B)") (class "Default")
      (node (ref "C7") (pin "1") (pinfunction "1_1") (pintype "bidirectional"))
      (node (ref "R2") (pin "2") (pinfunction "2_2") (pintype "bidirectional"))
      (node (ref "U21") (pin "9") (pinfunction "B_9") (pintype "bidirectional"))
      (node (ref "U6") (pin "4") (pinfunction "-_4") (pintype "bidirectional"))
    )
    (net (code "32") (name "Net-(U21-W)") (class "Default")
      (node (ref "R4") (pin "1") (pinfunction "1_1") (pintype "bidirectional"))
      (node (ref "U21") (pin "1") (pinfunction "W_1") (pintype "bidirectional"))
    )
    (net (code "33") (name "Net-(U22-W)") (class "Default")
      (node (ref "R10") (pin "1") (pinfunction "1_1") (pintype "bidirectional"))
      (node (ref "U22") (pin "1") (pinfunction "W_1") (pintype "bidirectional"))
    )
    (net (code "34") (name "POT_I2C_SCL") (class "Default")
      (node (ref "U19") (pin "5") (pinfunction "SCL_5") (pintype "bidirectional"))
      (node (ref "U21") (pin "5") (pinfunction "SCL_5") (pintype "bidirectional"))
      (node (ref "U22") (pin "5") (pinfunction "SCL_5") (pintype "bidirectional"))
    )
    (net (code "35") (name "POT_I2C_SDA") (class "Default")
      (node (ref "U19") (pin "4") (pinfunction "SDA_4") (pintype "bidirectional"))
      (node (ref "U21") (pin "4") (pinfunction "SDA_4") (pintype "bidirectional"))
      (node (ref "U22") (pin "4") (pinfunction "SDA_4") (pintype "bidirectional"))
    )
    (net (code "36") (name "PWR_ANA_3V3") (class "Default")
      (node (ref "C18") (pin "2") (pinfunction "2_2") (pintype "bidirectional"))
      (node (ref "C23") (pin "2") (pinfunction "2_2") (pintype "bidirectional"))
      (node (ref "C3") (pin "2") (pinfunction "2_2") (pintype "bidirectional"))
      (node (ref "U3") (pin "6") (pinfunction "AVDD_6") (pintype "bidirectional"))
      (node (ref "U7") (pin "6") (pinfunction "AVDD_6") (pintype "bidirectional"))
      (node (ref "U9") (pin "6") (pinfunction "AVDD_6") (pintype "bidirectional"))
    )
    (net (code "37") (name "PWR_ANA_5V") (class "Default")
      (node (ref "C21") (pin "2") (pinfunction "2_2") (pintype "bidirectional"))
      (node (ref "C34") (pin "2") (pinfunction "2_2") (pintype "bidirectional"))
      (node (ref "C53") (pin "2") (pinfunction "2_2") (pintype "bidirectional"))
      (node (ref "C55") (pin "2") (pinfunction "2_2") (pintype "bidirectional"))
      (node (ref "C57") (pin "2") (pinfunction "2_2") (pintype "bidirectional"))
      (node (ref "C6") (pin "2") (pinfunction "2_2") (pintype "bidirectional"))
      (node (ref "U10") (pin "5") (pinfunction "V+_5") (pintype "bidirectional"))
      (node (ref "U10") (pin "6") (pinfunction "V+_6") (pintype "bidirectional"))
      (node (ref "U19") (pin "8") (pinfunction "VDD_8") (pintype "bidirectional"))
      (node (ref "U21") (pin "8") (pinfunction "VDD_8") (pintype "bidirectional"))
      (node (ref "U22") (pin "8") (pinfunction "VDD_8") (pintype "bidirectional"))
      (node (ref "U6") (pin "5") (pinfunction "V+_5") (pintype "bidirectional"))
      (node (ref "U6") (pin "6") (pinfunction "V+_6") (pintype "bidirectional"))
      (node (ref "U8") (pin "5") (pinfunction "V+_5") (pintype "bidirectional"))
      (node (ref "U8") (pin "6") (pinfunction "V+_6") (pintype "bidirectional"))
    )
    (net (code "38") (name "PWR_ANA_10V") (class "Default")
      (node (ref "FB1") (pin "1") (pinfunction "1_1") (pintype "bidirectional"))
    )
    (net (code "39") (name "PWR_SENS_UNREG") (class "Default")
      (node (ref "C10") (pin "2") (pinfunction "2_2") (pintype "bidirectional"))
      (node (ref "Q2") (pin "1") (pinfunction "E_1") (pintype "bidirectional"))
    )
    (net (code "40") (name "PWR_SYS_3V3") (class "Default")
      (node (ref "C19") (pin "2") (pinfunction "2_2") (pintype "bidirectional"))
      (node (ref "C24") (pin "2") (pinfunction "2_2") (pintype "bidirectional"))
      (node (ref "C4") (pin "2") (pinfunction "2_2") (pintype "bidirectional"))
      (node (ref "C52") (pin "2") (pinfunction "2_2") (pintype "bidirectional"))
      (node (ref "C54") (pin "2") (pinfunction "2_2") (pintype "bidirectional"))
      (node (ref "C56") (pin "2") (pinfunction "2_2") (pintype "bidirectional"))
      (node (ref "U19") (pin "2") (pinfunction "A0_2") (pintype "bidirectional"))
      (node (ref "U19") (pin "6") (pinfunction "VIO_6") (pintype "bidirectional"))
      (node (ref "U21") (pin "6") (pinfunction "VIO_6") (pintype "bidirectional"))
      (node (ref "U22") (pin "3") (pinfunction "A1_3") (pintype "bidirectional"))
      (node (ref "U22") (pin "6") (pinfunction "VIO_6") (pintype "bidirectional"))
      (node (ref "U3") (pin "4") (pinfunction "DVDD_4") (pintype "bidirectional"))
      (node (ref "U7") (pin "4") (pinfunction "DVDD_4") (pintype "bidirectional"))
      (node (ref "U9") (pin "4") (pinfunction "DVDD_4") (pintype "bidirectional"))
    )
    (net (code "41") (name "SEN_OFFSET_OS1") (class "Default")
      (node (ref "U10") (pin "3") (pinfunction "+_3") (pintype "bidirectional"))
    )
    (net (code "42") (name "SEN_OFFSET_OS2") (class "Default")
      (node (ref "U8") (pin "3") (pinfunction "+_3") (pintype "bidirectional"))
    )
    (net (code "43") (name "SEN_OFFSET_OS3") (class "Default")
      (node (ref "U6") (pin "3") (pinfunction "+_3") (pintype "bidirectional"))
    )
    (net (code "44") (name "SEN_SIG_OS1") (class "Default")
      (node (ref "R9") (pin "1") (pinfunction "1_1") (pintype "bidirectional"))
      (node (ref "U1") (pin "21") (pinfunction "OS1_21") (pintype "bidirectional"))
    )
    (net (code "45") (name "SEN_SIG_OS2") (class "Default")
      (node (ref "R6") (pin "1") (pinfunction "1_1") (pintype "bidirectional"))
      (node (ref "U1") (pin "22") (pinfunction "OS2_22") (pintype "bidirectional"))
    )
    (net (code "46") (name "SEN_SIG_OS3") (class "Default")
      (node (ref "R2") (pin "1") (pinfunction "1_1") (pintype "bidirectional"))
      (node (ref "U1") (pin "1") (pinfunction "OS3_1") (pintype "bidirectional"))
    )
    (net (code "47") (name "unconnected-(C58-Pad2)") (class "Default")
      (node (ref "C58") (pin "2") (pinfunction "2_2") (pintype "bidirectional"))
    )
    (net (code "48") (name "unconnected-(C59-Pad2)") (class "Default")
      (node (ref "C59") (pin "2") (pinfunction "2_2") (pintype "bidirectional"))
    )
    (net (code "49") (name "unconnected-(C60-Pad2)") (class "Default")
      (node (ref "C60") (pin "2") (pinfunction "2_2") (pintype "bidirectional"))
    )
    (net (code "50") (name "unconnected-(C61-Pad2)") (class "Default")
      (node (ref "C61") (pin "2") (pinfunction "2_2") (pintype "bidirectional"))
    )
    (net (code "51") (name "unconnected-(C62-Pad2)") (class "Default")
      (node (ref "C62") (pin "2") (pinfunction "2_2") (pintype "bidirectional"))
    )
    (net (code "52") (name "unconnected-(C63-Pad2)") (class "Default")
      (node (ref "C63") (pin "2") (pinfunction "2_2") (pintype "bidirectional"))
    )
    (net (code "53") (name "unconnected-(CN3-Pad1)") (class "Default")
      (node (ref "CN3") (pin "1") (pinfunction "1_1") (pintype "bidirectional"))
    )
    (net (code "54") (name "unconnected-(CN3-Pad2)") (class "Default")
      (node (ref "CN3") (pin "2") (pinfunction "2_2") (pintype "bidirectional"))
    )
    (net (code "55") (name "unconnected-(CN3-Pad3)") (class "Default")
      (node (ref "CN3") (pin "3") (pinfunction "3_3") (pintype "bidirectional"))
    )
    (net (code "56") (name "unconnected-(CN3-Pad4)") (class "Default")
      (node (ref "CN3") (pin "4") (pinfunction "4_4") (pintype "bidirectional"))
    )
    (net (code "57") (name "unconnected-(CN3-Pad5)") (class "Default")
      (node (ref "CN3") (pin "5") (pinfunction "5_5") (pintype "bidirectional"))
    )
    (net (code "58") (name "unconnected-(CN3-Pad6)") (class "Default")
      (node (ref "CN3") (pin "6") (pinfunction "6_6") (pintype "bidirectional"))
    )
    (net (code "59") (name "unconnected-(CN3-Pad7)") (class "Default")
      (node (ref "CN3") (pin "7") (pinfunction "7_7") (pintype "bidirectional"))
    )
    (net (code "60") (name "unconnected-(CN3-Pad8)") (class "Default")
      (node (ref "CN3") (pin "8") (pinfunction "8_8") (pintype "bidirectional"))
    )
    (net (code "61") (name "unconnected-(CN3-Pad9)") (class "Default")
      (node (ref "CN3") (pin "9") (pinfunction "9_9") (pintype "bidirectional"))
    )
    (net (code "62") (name "unconnected-(CN3-Pad10)") (class "Default")
      (node (ref "CN3") (pin "10") (pinfunction "10_10") (pintype "bidirectional"))
    )
    (net (code "63") (name "unconnected-(CN3-Pad11)") (class "Default")
      (node (ref "CN3") (pin "11") (pinfunction "11_11") (pintype "bidirectional"))
    )
    (net (code "64") (name "unconnected-(CN3-Pad12)") (class "Default")
      (node (ref "CN3") (pin "12") (pinfunction "12_12") (pintype "bidirectional"))
    )
    (net (code "65") (name "unconnected-(CN3-Pad13)") (class "Default")
      (node (ref "CN3") (pin "13") (pinfunction "13_13") (pintype "bidirectional"))
    )
    (net (code "66") (name "unconnected-(CN3-Pad14)") (class "Default")
      (node (ref "CN3") (pin "14") (pinfunction "14_14") (pintype "bidirectional"))
    )
    (net (code "67") (name "unconnected-(CN3-Pad15)") (class "Default")
      (node (ref "CN3") (pin "15") (pinfunction "15_15") (pintype "bidirectional"))
    )
    (net (code "68") (name "unconnected-(FB2-Pad1)") (class "Default")
      (node (ref "FB2") (pin "1") (pinfunction "1_1") (pintype "bidirectional"))
    )
    (net (code "69") (name "unconnected-(U11A-GND-Pad2)") (class "Default")
      (node (ref "U11") (pin "2") (pinfunction "GND_2") (pintype "bidirectional"))
    )
    (net (code "70") (name "unconnected-(U11A-V+-Pad5)") (class "Default")
      (node (ref "U11") (pin "5") (pinfunction "V+_5") (pintype "bidirectional"))
    )
    (net (code "71") (name "unconnected-(U12A-GND-Pad2)") (class "Default")
      (node (ref "U12") (pin "2") (pinfunction "GND_2") (pintype "bidirectional"))
    )
    (net (code "72") (name "unconnected-(U12A-V+-Pad5)") (class "Default")
      (node (ref "U12") (pin "5") (pinfunction "V+_5") (pintype "bidirectional"))
    )
    (net (code "73") (name "unconnected-(U13A-GND-Pad2)") (class "Default")
      (node (ref "U13") (pin "2") (pinfunction "GND_2") (pintype "bidirectional"))
    )
    (net (code "74") (name "unconnected-(U13A-V+-Pad5)") (class "Default")
      (node (ref "U13") (pin "5") (pinfunction "V+_5") (pintype "bidirectional"))
    )
    (net (code "75") (name "unconnected-(U13B-A-Pad1)") (class "Default")
      (node (ref "U13") (pin "1") (pinfunction "A_1") (pintype "bidirectional"))
    )
    (net (code "76") (name "unconnected-(U13C-A-Pad3)") (class "Default")
      (node (ref "U13") (pin "3") (pinfunction "A_3") (pintype "bidirectional"))
    )
    (net (code "77") (name "unconnected-(U14A-GND-Pad2)") (class "Default")
      (node (ref "U14") (pin "2") (pinfunction "GND_2") (pintype "bidirectional"))
    )
    (net (code "78") (name "unconnected-(U14A-V+-Pad5)") (class "Default")
      (node (ref "U14") (pin "5") (pinfunction "V+_5") (pintype "bidirectional"))
    )
    (net (code "79") (name "unconnected-(U14B-A-Pad1)") (class "Default")
      (node (ref "U14") (pin "1") (pinfunction "A_1") (pintype "bidirectional"))
    )
    (net (code "80") (name "unconnected-(U14C-A-Pad3)") (class "Default")
      (node (ref "U14") (pin "3") (pinfunction "A_3") (pintype "bidirectional"))
    )
    (net (code "81") (name "unconnected-(U15A-GND-Pad2)") (class "Default")
      (node (ref "U15") (pin "2") (pinfunction "GND_2") (pintype "bidirectional"))
    )
    (net (code "82") (name "unconnected-(U15A-V+-Pad5)") (class "Default")
      (node (ref "U15") (pin "5") (pinfunction "V+_5") (pintype "bidirectional"))
    )
    (net (code "83") (name "unconnected-(U15B-A-Pad1)") (class "Default")
      (node (ref "U15") (pin "1") (pinfunction "A_1") (pintype "bidirectional"))
    )
    (net (code "84") (name "unconnected-(U15C-A-Pad3)") (class "Default")
      (node (ref "U15") (pin "3") (pinfunction "A_3") (pintype "bidirectional"))
    )
    (net (code "85") (name "unconnected-(U19-A-Pad10)") (class "Default")
      (node (ref "U19") (pin "10") (pinfunction "A_10") (pintype "bidirectional"))
    )
    (net (code "86") (name "unconnected-(U20A-GND-Pad2)") (class "Default")
      (node (ref "U20") (pin "2") (pinfunction "GND_2") (pintype "bidirectional"))
    )
    (net (code "87") (name "unconnected-(U20A-V+-Pad5)") (class "Default")
      (node (ref "U20") (pin "5") (pinfunction "V+_5") (pintype "bidirectional"))
    )
    (net (code "88") (name "unconnected-(U20B-A-Pad1)") (class "Default")
      (node (ref "U20") (pin "1") (pinfunction "A_1") (pintype "bidirectional"))
    )
    (net (code "89") (name "unconnected-(U20C-A-Pad3)") (class "Default")
      (node (ref "U20") (pin "3") (pinfunction "A_3") (pintype "bidirectional"))
    )
    (net (code "90") (name "unconnected-(U21-A-Pad10)") (class "Default")
      (node (ref "U21") (pin "10") (pinfunction "A_10") (pintype "bidirectional"))
    )
    (net (code "91") (name "unconnected-(U22-A-Pad10)") (class "Default")
      (node (ref "U22") (pin "10") (pinfunction "A_10") (pintype "bidirectional"))
    )
  )
)
